# Output.net
KiCad netlist of a schematic drawn in Altium Designer
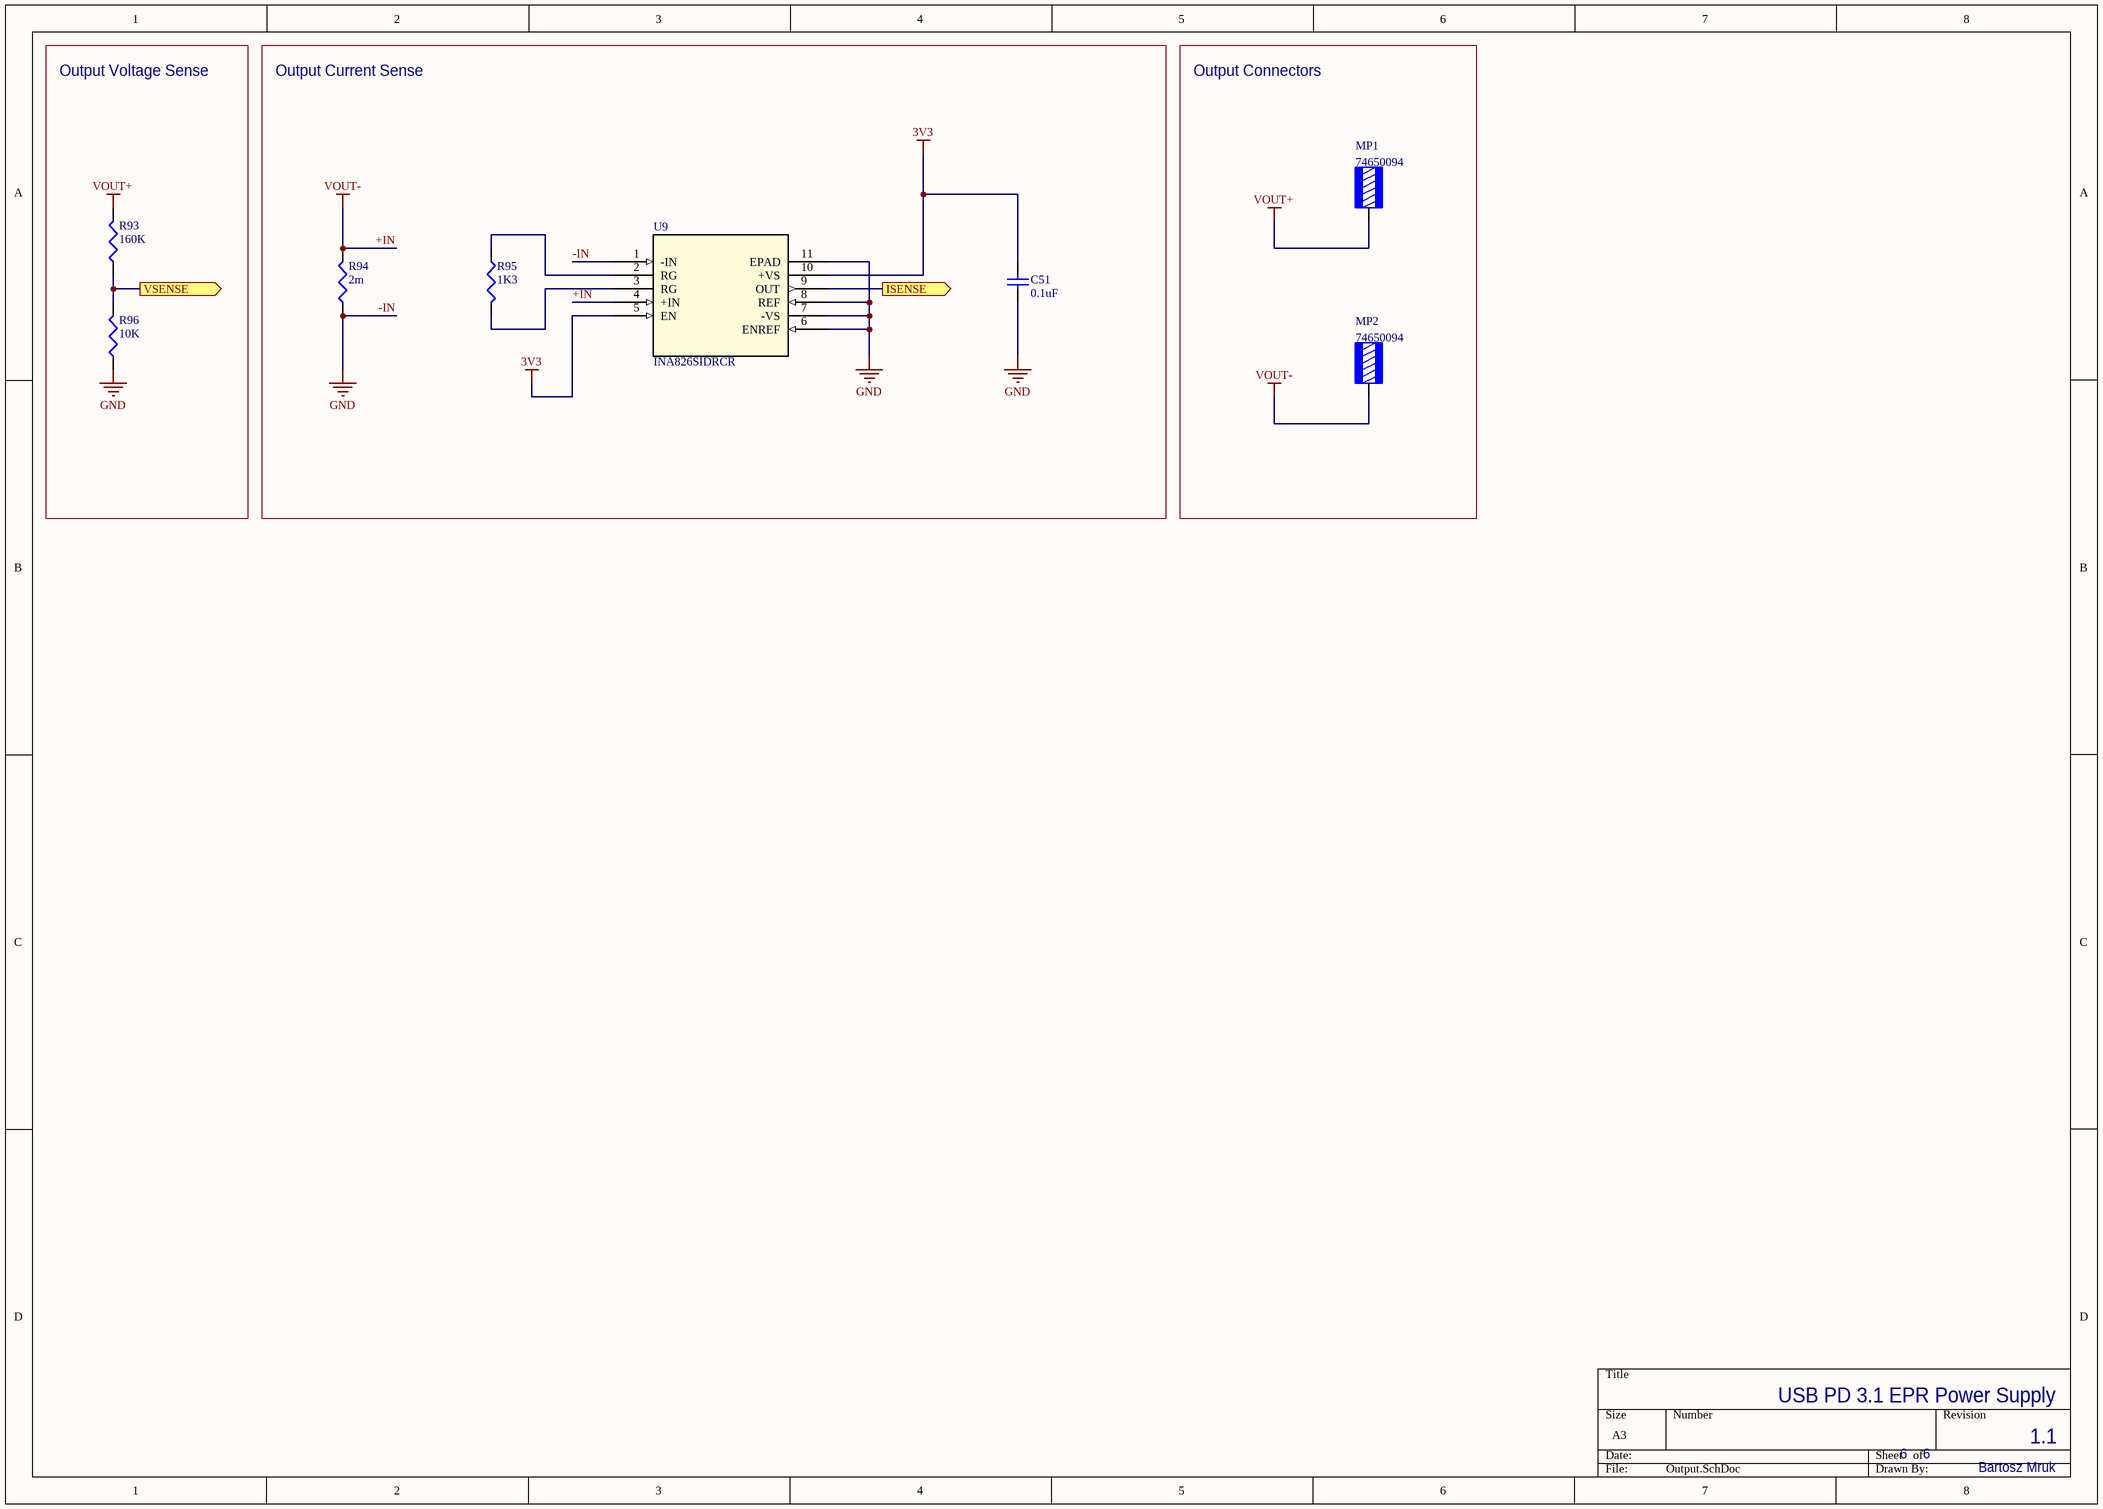
[diagram p0: Output.SchDoc]

(export (version "E")
  (design (tool "Eeschema 10.0.6"))
  (components
    (comp (ref "C51")
      (value "0.1uF")
      (footprint "1608[0603]")
      (description "Capacitor (Semiconductor SIM Model)")
      (fields (field (name "PUBLISHER") "Altium Limited"))
      (libsource (lib "Miscellaneous Devices") (part "Cap Semi"))
    )
    (comp (ref "MP1")
      (value "74650094")
      (footprint "74650094")
      (description "WP-THRBU REDCUBE Bush, THR_open")
      (libsource (lib "Altium Content Vault") (part "WP-THRBU_through hole"))
    )
    (comp (ref "MP2")
      (value "74650094")
      (footprint "74650094")
      (description "WP-THRBU REDCUBE Bush, THR_open")
      (libsource (lib "Altium Content Vault") (part "WP-THRBU_through hole"))
    )
    (comp (ref "R93")
      (value "160K")
      (footprint "J1-0603")
      (description "Resistor")
      (fields (field (name "Comment") "Res3") (field (name "PUBLISHER") "Altium Limited"))
      (libsource (lib "Miscellaneous Devices") (part "Res3"))
    )
    (comp (ref "R94")
      (value "2m")
      (footprint "RESC6332")
      (description "Resistor")
      (fields (field (name "Comment") "Res3") (field (name "PUBLISHER") "Altium Limited"))
      (libsource (lib "Miscellaneous Devices") (part "Res3"))
    )
    (comp (ref "R95")
      (value "1K3")
      (footprint "J1-0603")
      (description "Resistor")
      (fields (field (name "Comment") "Res3") (field (name "PUBLISHER") "Altium Limited"))
      (libsource (lib "Miscellaneous Devices") (part "Res3"))
    )
    (comp (ref "R96")
      (value "10K")
      (footprint "J1-0603")
      (description "Resistor")
      (fields (field (name "Comment") "Res3") (field (name "PUBLISHER") "Altium Limited"))
      (libsource (lib "Miscellaneous Devices") (part "Res3"))
    )
    (comp (ref "U9")
      (value "INA826SIDRCR")
      (footprint "DRC10_TEX")
      (description "200 渭A, 36V, Rail-to-Rail Out Instrumentation Amplifier with Shutdown 10-VSON -40 to 125")
      (fields (field (name "COPYRIGHT") "Copyright (C) 2025 Ultra Librarian. All rights reserved."))
      (libsource (lib "INA826SIDRCR") (part "INA826SIDRCR"))
    )
  )
  (nets
    (net (code "1") (name "/ISENSE") (class "Default")
      (node (ref "U9") (pin "9") (pinfunction "OUT_9") (pintype "output"))
    )
    (net (code "2") (name "/VSENSE") (class "Default")
      (node (ref "R93") (pin "1") (pinfunction "1_1") (pintype "passive"))
      (node (ref "R96") (pin "2") (pinfunction "2_2") (pintype "passive"))
    )
    (net (code "3") (name "3V3") (class "Default")
      (node (ref "C51") (pin "2") (pinfunction "2_2") (pintype "passive"))
      (node (ref "U9") (pin "10") (pinfunction "+VS_10") (pintype "power_in"))
      (node (ref "U9") (pin "5") (pinfunction "EN_5") (pintype "input"))
    )
    (net (code "4") (name "GND") (class "Default")
      (node (ref "C51") (pin "1") (pinfunction "1_1") (pintype "passive"))
      (node (ref "R94") (pin "1") (pinfunction "1_1") (pintype "passive"))
      (node (ref "R96") (pin "1") (pinfunction "1_1") (pintype "passive"))
      (node (ref "U9") (pin "1") (pinfunction "-IN_1") (pintype "input"))
      (node (ref "U9") (pin "11") (pinfunction "EPAD_11") (pintype "passive"))
      (node (ref "U9") (pin "6") (pinfunction "ENREF_6") (pintype "input"))
      (node (ref "U9") (pin "7") (pinfunction "-VS_7") (pintype "power_in"))
      (node (ref "U9") (pin "8") (pinfunction "REF_8") (pintype "input"))
    )
    (net (code "5") (name "Net-(R95-Pad1)") (class "Default")
      (node (ref "R95") (pin "1") (pinfunction "1_1") (pintype "passive"))
      (node (ref "U9") (pin "2") (pinfunction "RG_2") (pintype "passive"))
    )
    (net (code "6") (name "Net-(R95-Pad2)") (class "Default")
      (node (ref "R95") (pin "2") (pinfunction "2_2") (pintype "passive"))
      (node (ref "U9") (pin "3") (pinfunction "RG_3") (pintype "passive"))
    )
    (net (code "7") (name "VOUT+") (class "Default")
      (node (ref "MP1") (pin "1") (pinfunction "1_1") (pintype "passive"))
      (node (ref "R93") (pin "2") (pinfunction "2_2") (pintype "passive"))
    )
    (net (code "8") (name "VOUT-") (class "Default")
      (node (ref "MP2") (pin "1") (pinfunction "1_1") (pintype "passive"))
      (node (ref "R94") (pin "2") (pinfunction "2_2") (pintype "passive"))
      (node (ref "U9") (pin "4") (pinfunction "+IN_4") (pintype "input"))
    )
  )
)
